# Expanssion_Bay.net
KiCad netlist of a schematic drawn in EAGLE
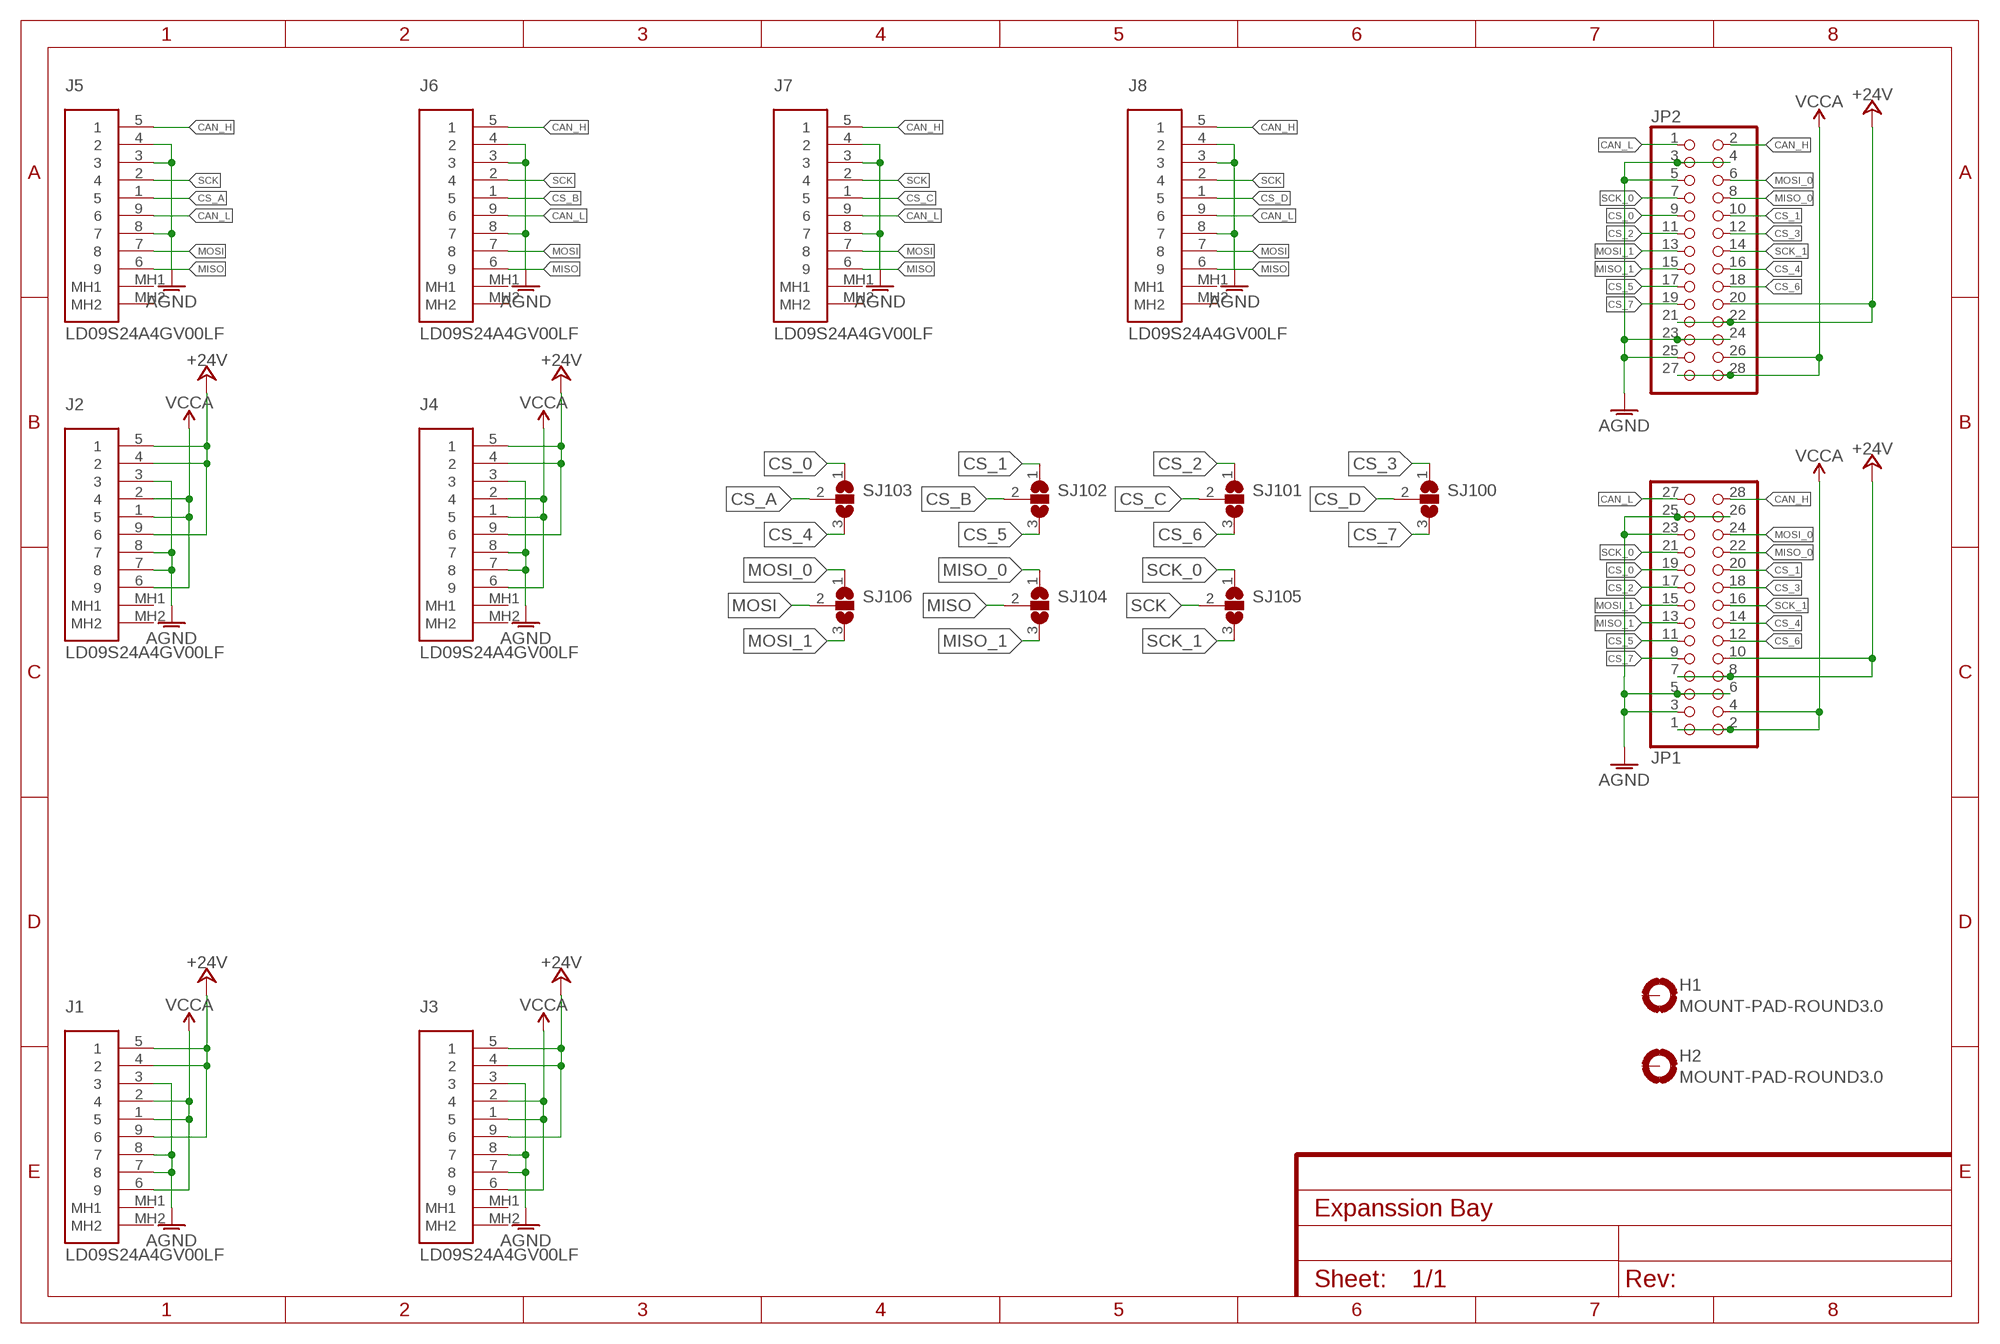
[diagram p0: schematic, sheet 1]

(export (version "E")
  (design (tool "Eeschema 10.0.6"))
  (components
    (comp (ref "H1")
      (value "MOUNT-PAD-ROUND3.0")
      (footprint "eagle-import:3,0-PAD")
      (libsource (lib "eagle-import") (part "MOUNT-PAD-ROUND3.0"))
    )
    (comp (ref "H2")
      (value "MOUNT-PAD-ROUND3.0")
      (footprint "eagle-import:3,0-PAD")
      (libsource (lib "eagle-import") (part "MOUNT-PAD-ROUND3.0"))
    )
    (comp (ref "J1")
      (value "LD09S24A4GV00LF")
      (footprint "eagle-import:LD09S24A4GV00LF")
      (fields
        (field (name "DIGIKEY_PART_NUMBER") "609-5190-ND")
        (field (name "MANUFACTURER") "Amphenol ICC (FCI)")
        (field (name "CREATED_BY") "PCBLayout.com")
      )
      (libsource (lib "eagle-import") (part "LD09S24A4GV00LF"))
    )
    (comp (ref "J2")
      (value "LD09S24A4GV00LF")
      (footprint "eagle-import:LD09S24A4GV00LF")
      (fields
        (field (name "DIGIKEY_PART_NUMBER") "609-5190-ND")
        (field (name "MANUFACTURER") "Amphenol ICC (FCI)")
        (field (name "CREATED_BY") "PCBLayout.com")
      )
      (libsource (lib "eagle-import") (part "LD09S24A4GV00LF"))
    )
    (comp (ref "J3")
      (value "LD09S24A4GV00LF")
      (footprint "eagle-import:LD09S24A4GV00LF")
      (fields
        (field (name "DIGIKEY_PART_NUMBER") "609-5190-ND")
        (field (name "MANUFACTURER") "Amphenol ICC (FCI)")
        (field (name "CREATED_BY") "PCBLayout.com")
      )
      (libsource (lib "eagle-import") (part "LD09S24A4GV00LF"))
    )
    (comp (ref "J4")
      (value "LD09S24A4GV00LF")
      (footprint "eagle-import:LD09S24A4GV00LF")
      (fields
        (field (name "DIGIKEY_PART_NUMBER") "609-5190-ND")
        (field (name "MANUFACTURER") "Amphenol ICC (FCI)")
        (field (name "CREATED_BY") "PCBLayout.com")
      )
      (libsource (lib "eagle-import") (part "LD09S24A4GV00LF"))
    )
    (comp (ref "J5")
      (value "LD09S24A4GV00LF")
      (footprint "eagle-import:LD09S24A4GV00LF")
      (fields
        (field (name "DIGIKEY_PART_NUMBER") "609-5190-ND")
        (field (name "MANUFACTURER") "Amphenol ICC (FCI)")
        (field (name "CREATED_BY") "PCBLayout.com")
      )
      (libsource (lib "eagle-import") (part "LD09S24A4GV00LF"))
    )
    (comp (ref "J6")
      (value "LD09S24A4GV00LF")
      (footprint "eagle-import:LD09S24A4GV00LF")
      (fields
        (field (name "DIGIKEY_PART_NUMBER") "609-5190-ND")
        (field (name "MANUFACTURER") "Amphenol ICC (FCI)")
        (field (name "CREATED_BY") "PCBLayout.com")
      )
      (libsource (lib "eagle-import") (part "LD09S24A4GV00LF"))
    )
    (comp (ref "J7")
      (value "LD09S24A4GV00LF")
      (footprint "eagle-import:LD09S24A4GV00LF")
      (fields
        (field (name "DIGIKEY_PART_NUMBER") "609-5190-ND")
        (field (name "MANUFACTURER") "Amphenol ICC (FCI)")
        (field (name "CREATED_BY") "PCBLayout.com")
      )
      (libsource (lib "eagle-import") (part "LD09S24A4GV00LF"))
    )
    (comp (ref "J8")
      (value "LD09S24A4GV00LF")
      (footprint "eagle-import:LD09S24A4GV00LF")
      (fields
        (field (name "DIGIKEY_PART_NUMBER") "609-5190-ND")
        (field (name "MANUFACTURER") "Amphenol ICC (FCI)")
        (field (name "CREATED_BY") "PCBLayout.com")
      )
      (libsource (lib "eagle-import") (part "LD09S24A4GV00LF"))
    )
    (comp (ref "JP1")
      (value "PINHD-2X14/90")
      (footprint "eagle-import:2X14_90")
      (libsource (lib "eagle-import") (part "PINHD-2X14/90"))
    )
    (comp (ref "JP2")
      (value "PINHD-2X14/90")
      (footprint "eagle-import:2X14_90")
      (libsource (lib "eagle-import") (part "PINHD-2X14/90"))
    )
    (comp (ref "SJ100")
      (value "SJ2W")
      (footprint "eagle-import:SJ_2")
      (libsource (lib "eagle-import") (part "SJ2W"))
    )
    (comp (ref "SJ101")
      (value "SJ2W")
      (footprint "eagle-import:SJ_2")
      (libsource (lib "eagle-import") (part "SJ2W"))
    )
    (comp (ref "SJ102")
      (value "SJ2W")
      (footprint "eagle-import:SJ_2")
      (libsource (lib "eagle-import") (part "SJ2W"))
    )
    (comp (ref "SJ103")
      (value "SJ2W")
      (footprint "eagle-import:SJ_2")
      (libsource (lib "eagle-import") (part "SJ2W"))
    )
    (comp (ref "SJ104")
      (value "SJ2W")
      (footprint "eagle-import:SJ_2")
      (libsource (lib "eagle-import") (part "SJ2W"))
    )
    (comp (ref "SJ105")
      (value "SJ2W")
      (footprint "eagle-import:SJ_2")
      (libsource (lib "eagle-import") (part "SJ2W"))
    )
    (comp (ref "SJ106")
      (value "SJ2W")
      (footprint "eagle-import:SJ_2")
      (libsource (lib "eagle-import") (part "SJ2W"))
    )
  )
  (nets
    (net (code "1") (name "+24V") (class "Default")
      (node (ref "J1") (pin "4") (pinfunction "2_4") (pintype "passive"))
      (node (ref "J1") (pin "5") (pinfunction "1_5") (pintype "passive"))
      (node (ref "J1") (pin "9") (pinfunction "6_9") (pintype "passive"))
      (node (ref "J2") (pin "4") (pinfunction "2_4") (pintype "passive"))
      (node (ref "J2") (pin "5") (pinfunction "1_5") (pintype "passive"))
      (node (ref "J2") (pin "9") (pinfunction "6_9") (pintype "passive"))
      (node (ref "J3") (pin "4") (pinfunction "2_4") (pintype "passive"))
      (node (ref "J3") (pin "5") (pinfunction "1_5") (pintype "passive"))
      (node (ref "J3") (pin "9") (pinfunction "6_9") (pintype "passive"))
      (node (ref "J4") (pin "4") (pinfunction "2_4") (pintype "passive"))
      (node (ref "J4") (pin "5") (pinfunction "1_5") (pintype "passive"))
      (node (ref "J4") (pin "9") (pinfunction "6_9") (pintype "passive"))
      (node (ref "JP1") (pin "10") (pinfunction "10_10") (pintype "passive"))
      (node (ref "JP1") (pin "7") (pinfunction "7_7") (pintype "passive"))
      (node (ref "JP1") (pin "8") (pinfunction "8_8") (pintype "passive"))
      (node (ref "JP2") (pin "20") (pinfunction "20_20") (pintype "passive"))
      (node (ref "JP2") (pin "21") (pinfunction "21_21") (pintype "passive"))
      (node (ref "JP2") (pin "22") (pinfunction "22_22") (pintype "passive"))
    )
    (net (code "2") (name "AGND") (class "Default")
      (node (ref "J1") (pin "3") (pinfunction "3_3") (pintype "passive"))
      (node (ref "J1") (pin "7") (pinfunction "8_7") (pintype "passive"))
      (node (ref "J1") (pin "8") (pinfunction "7_8") (pintype "passive"))
      (node (ref "J2") (pin "3") (pinfunction "3_3") (pintype "passive"))
      (node (ref "J2") (pin "7") (pinfunction "8_7") (pintype "passive"))
      (node (ref "J2") (pin "8") (pinfunction "7_8") (pintype "passive"))
      (node (ref "J3") (pin "3") (pinfunction "3_3") (pintype "passive"))
      (node (ref "J3") (pin "7") (pinfunction "8_7") (pintype "passive"))
      (node (ref "J3") (pin "8") (pinfunction "7_8") (pintype "passive"))
      (node (ref "J4") (pin "3") (pinfunction "3_3") (pintype "passive"))
      (node (ref "J4") (pin "7") (pinfunction "8_7") (pintype "passive"))
      (node (ref "J4") (pin "8") (pinfunction "7_8") (pintype "passive"))
      (node (ref "J5") (pin "3") (pinfunction "3_3") (pintype "passive"))
      (node (ref "J5") (pin "4") (pinfunction "2_4") (pintype "passive"))
      (node (ref "J5") (pin "8") (pinfunction "7_8") (pintype "passive"))
      (node (ref "J6") (pin "3") (pinfunction "3_3") (pintype "passive"))
      (node (ref "J6") (pin "4") (pinfunction "2_4") (pintype "passive"))
      (node (ref "J6") (pin "8") (pinfunction "7_8") (pintype "passive"))
      (node (ref "J7") (pin "3") (pinfunction "3_3") (pintype "passive"))
      (node (ref "J7") (pin "4") (pinfunction "2_4") (pintype "passive"))
      (node (ref "J7") (pin "8") (pinfunction "7_8") (pintype "passive"))
      (node (ref "J8") (pin "3") (pinfunction "3_3") (pintype "passive"))
      (node (ref "J8") (pin "4") (pinfunction "2_4") (pintype "passive"))
      (node (ref "J8") (pin "8") (pinfunction "7_8") (pintype "passive"))
      (node (ref "JP1") (pin "23") (pinfunction "23_23") (pintype "passive"))
      (node (ref "JP1") (pin "25") (pinfunction "25_25") (pintype "passive"))
      (node (ref "JP1") (pin "26") (pinfunction "26_26") (pintype "passive"))
      (node (ref "JP1") (pin "3") (pinfunction "3_3") (pintype "passive"))
      (node (ref "JP1") (pin "5") (pinfunction "5_5") (pintype "passive"))
      (node (ref "JP1") (pin "6") (pinfunction "6_6") (pintype "passive"))
      (node (ref "JP2") (pin "23") (pinfunction "23_23") (pintype "passive"))
      (node (ref "JP2") (pin "24") (pinfunction "24_24") (pintype "passive"))
      (node (ref "JP2") (pin "25") (pinfunction "25_25") (pintype "passive"))
      (node (ref "JP2") (pin "3") (pinfunction "3_3") (pintype "passive"))
      (node (ref "JP2") (pin "4") (pinfunction "4_4") (pintype "passive"))
      (node (ref "JP2") (pin "5") (pinfunction "5_5") (pintype "passive"))
    )
    (net (code "3") (name "CAN_H") (class "Default")
      (node (ref "J5") (pin "5") (pinfunction "1_5") (pintype "passive"))
      (node (ref "J6") (pin "5") (pinfunction "1_5") (pintype "passive"))
      (node (ref "J7") (pin "5") (pinfunction "1_5") (pintype "passive"))
      (node (ref "J8") (pin "5") (pinfunction "1_5") (pintype "passive"))
      (node (ref "JP1") (pin "28") (pinfunction "28_28") (pintype "passive"))
      (node (ref "JP2") (pin "2") (pinfunction "2_2") (pintype "passive"))
    )
    (net (code "4") (name "CAN_L") (class "Default")
      (node (ref "J5") (pin "9") (pinfunction "6_9") (pintype "passive"))
      (node (ref "J6") (pin "9") (pinfunction "6_9") (pintype "passive"))
      (node (ref "J7") (pin "9") (pinfunction "6_9") (pintype "passive"))
      (node (ref "J8") (pin "9") (pinfunction "6_9") (pintype "passive"))
      (node (ref "JP1") (pin "27") (pinfunction "27_27") (pintype "passive"))
      (node (ref "JP2") (pin "1") (pinfunction "1_1") (pintype "passive"))
    )
    (net (code "5") (name "CS_0") (class "Default")
      (node (ref "JP1") (pin "19") (pinfunction "19_19") (pintype "passive"))
      (node (ref "JP2") (pin "9") (pinfunction "9_9") (pintype "passive"))
      (node (ref "SJ103") (pin "1") (pinfunction "1_1") (pintype "passive"))
    )
    (net (code "6") (name "CS_1") (class "Default")
      (node (ref "JP1") (pin "20") (pinfunction "20_20") (pintype "passive"))
      (node (ref "JP2") (pin "10") (pinfunction "10_10") (pintype "passive"))
      (node (ref "SJ102") (pin "1") (pinfunction "1_1") (pintype "passive"))
    )
    (net (code "7") (name "CS_2") (class "Default")
      (node (ref "JP1") (pin "17") (pinfunction "17_17") (pintype "passive"))
      (node (ref "JP2") (pin "11") (pinfunction "11_11") (pintype "passive"))
      (node (ref "SJ101") (pin "1") (pinfunction "1_1") (pintype "passive"))
    )
    (net (code "8") (name "CS_3") (class "Default")
      (node (ref "JP1") (pin "18") (pinfunction "18_18") (pintype "passive"))
      (node (ref "JP2") (pin "12") (pinfunction "12_12") (pintype "passive"))
      (node (ref "SJ100") (pin "1") (pinfunction "1_1") (pintype "passive"))
    )
    (net (code "9") (name "CS_4") (class "Default")
      (node (ref "JP1") (pin "14") (pinfunction "14_14") (pintype "passive"))
      (node (ref "JP2") (pin "16") (pinfunction "16_16") (pintype "passive"))
      (node (ref "SJ103") (pin "3") (pinfunction "3_3") (pintype "passive"))
    )
    (net (code "10") (name "CS_5") (class "Default")
      (node (ref "JP1") (pin "11") (pinfunction "11_11") (pintype "passive"))
      (node (ref "JP2") (pin "17") (pinfunction "17_17") (pintype "passive"))
      (node (ref "SJ102") (pin "3") (pinfunction "3_3") (pintype "passive"))
    )
    (net (code "11") (name "CS_6") (class "Default")
      (node (ref "JP1") (pin "12") (pinfunction "12_12") (pintype "passive"))
      (node (ref "JP2") (pin "18") (pinfunction "18_18") (pintype "passive"))
      (node (ref "SJ101") (pin "3") (pinfunction "3_3") (pintype "passive"))
    )
    (net (code "12") (name "CS_7") (class "Default")
      (node (ref "JP1") (pin "9") (pinfunction "9_9") (pintype "passive"))
      (node (ref "JP2") (pin "19") (pinfunction "19_19") (pintype "passive"))
      (node (ref "SJ100") (pin "3") (pinfunction "3_3") (pintype "passive"))
    )
    (net (code "13") (name "CS_A") (class "Default")
      (node (ref "J5") (pin "1") (pinfunction "5_1") (pintype "passive"))
      (node (ref "SJ103") (pin "2") (pinfunction "2_2") (pintype "passive"))
    )
    (net (code "14") (name "CS_B") (class "Default")
      (node (ref "J6") (pin "1") (pinfunction "5_1") (pintype "passive"))
      (node (ref "SJ102") (pin "2") (pinfunction "2_2") (pintype "passive"))
    )
    (net (code "15") (name "CS_C") (class "Default")
      (node (ref "J7") (pin "1") (pinfunction "5_1") (pintype "passive"))
      (node (ref "SJ101") (pin "2") (pinfunction "2_2") (pintype "passive"))
    )
    (net (code "16") (name "CS_D") (class "Default")
      (node (ref "J8") (pin "1") (pinfunction "5_1") (pintype "passive"))
      (node (ref "SJ100") (pin "2") (pinfunction "2_2") (pintype "passive"))
    )
    (net (code "17") (name "MISO") (class "Default")
      (node (ref "J5") (pin "6") (pinfunction "9_6") (pintype "passive"))
      (node (ref "J6") (pin "6") (pinfunction "9_6") (pintype "passive"))
      (node (ref "J7") (pin "6") (pinfunction "9_6") (pintype "passive"))
      (node (ref "J8") (pin "6") (pinfunction "9_6") (pintype "passive"))
      (node (ref "SJ104") (pin "2") (pinfunction "2_2") (pintype "passive"))
    )
    (net (code "18") (name "MISO_0") (class "Default")
      (node (ref "JP1") (pin "22") (pinfunction "22_22") (pintype "passive"))
      (node (ref "JP2") (pin "8") (pinfunction "8_8") (pintype "passive"))
      (node (ref "SJ104") (pin "1") (pinfunction "1_1") (pintype "passive"))
    )
    (net (code "19") (name "MISO_1") (class "Default")
      (node (ref "JP1") (pin "13") (pinfunction "13_13") (pintype "passive"))
      (node (ref "JP2") (pin "15") (pinfunction "15_15") (pintype "passive"))
      (node (ref "SJ104") (pin "3") (pinfunction "3_3") (pintype "passive"))
    )
    (net (code "20") (name "MOSI") (class "Default")
      (node (ref "J5") (pin "7") (pinfunction "8_7") (pintype "passive"))
      (node (ref "J6") (pin "7") (pinfunction "8_7") (pintype "passive"))
      (node (ref "J7") (pin "7") (pinfunction "8_7") (pintype "passive"))
      (node (ref "J8") (pin "7") (pinfunction "8_7") (pintype "passive"))
      (node (ref "SJ106") (pin "2") (pinfunction "2_2") (pintype "passive"))
    )
    (net (code "21") (name "MOSI_0") (class "Default")
      (node (ref "JP1") (pin "24") (pinfunction "24_24") (pintype "passive"))
      (node (ref "JP2") (pin "6") (pinfunction "6_6") (pintype "passive"))
      (node (ref "SJ106") (pin "1") (pinfunction "1_1") (pintype "passive"))
    )
    (net (code "22") (name "MOSI_1") (class "Default")
      (node (ref "JP1") (pin "15") (pinfunction "15_15") (pintype "passive"))
      (node (ref "JP2") (pin "13") (pinfunction "13_13") (pintype "passive"))
      (node (ref "SJ106") (pin "3") (pinfunction "3_3") (pintype "passive"))
    )
    (net (code "23") (name "SCK") (class "Default")
      (node (ref "J5") (pin "2") (pinfunction "4_2") (pintype "passive"))
      (node (ref "J6") (pin "2") (pinfunction "4_2") (pintype "passive"))
      (node (ref "J7") (pin "2") (pinfunction "4_2") (pintype "passive"))
      (node (ref "J8") (pin "2") (pinfunction "4_2") (pintype "passive"))
      (node (ref "SJ105") (pin "2") (pinfunction "2_2") (pintype "passive"))
    )
    (net (code "24") (name "SCK_0") (class "Default")
      (node (ref "JP1") (pin "21") (pinfunction "21_21") (pintype "passive"))
      (node (ref "JP2") (pin "7") (pinfunction "7_7") (pintype "passive"))
      (node (ref "SJ105") (pin "1") (pinfunction "1_1") (pintype "passive"))
    )
    (net (code "25") (name "SCK_1") (class "Default")
      (node (ref "JP1") (pin "16") (pinfunction "16_16") (pintype "passive"))
      (node (ref "JP2") (pin "14") (pinfunction "14_14") (pintype "passive"))
      (node (ref "SJ105") (pin "3") (pinfunction "3_3") (pintype "passive"))
    )
    (net (code "26") (name "VCCA") (class "Default")
      (node (ref "J1") (pin "1") (pinfunction "5_1") (pintype "passive"))
      (node (ref "J1") (pin "2") (pinfunction "4_2") (pintype "passive"))
      (node (ref "J1") (pin "6") (pinfunction "9_6") (pintype "passive"))
      (node (ref "J2") (pin "1") (pinfunction "5_1") (pintype "passive"))
      (node (ref "J2") (pin "2") (pinfunction "4_2") (pintype "passive"))
      (node (ref "J2") (pin "6") (pinfunction "9_6") (pintype "passive"))
      (node (ref "J3") (pin "1") (pinfunction "5_1") (pintype "passive"))
      (node (ref "J3") (pin "2") (pinfunction "4_2") (pintype "passive"))
      (node (ref "J3") (pin "6") (pinfunction "9_6") (pintype "passive"))
      (node (ref "J4") (pin "1") (pinfunction "5_1") (pintype "passive"))
      (node (ref "J4") (pin "2") (pinfunction "4_2") (pintype "passive"))
      (node (ref "J4") (pin "6") (pinfunction "9_6") (pintype "passive"))
      (node (ref "JP1") (pin "1") (pinfunction "1_1") (pintype "passive"))
      (node (ref "JP1") (pin "2") (pinfunction "2_2") (pintype "passive"))
      (node (ref "JP1") (pin "4") (pinfunction "4_4") (pintype "passive"))
      (node (ref "JP2") (pin "26") (pinfunction "26_26") (pintype "passive"))
      (node (ref "JP2") (pin "27") (pinfunction "27_27") (pintype "passive"))
      (node (ref "JP2") (pin "28") (pinfunction "28_28") (pintype "passive"))
    )
    (net (code "27") (name "unconnected-(H1-MOUNT-PadB3,0)") (class "Default")
      (node (ref "H1") (pin "B3,0") (pinfunction "MOUNT_B3,0") (pintype "passive"))
    )
    (net (code "28") (name "unconnected-(H2-MOUNT-PadB3,0)") (class "Default")
      (node (ref "H2") (pin "B3,0") (pinfunction "MOUNT_B3,0") (pintype "passive"))
    )
    (net (code "29") (name "unconnected-(J1-PadMH1)") (class "Default")
      (node (ref "J1") (pin "MH1") (pinfunction "MH1_MH1") (pintype "passive"))
    )
    (net (code "30") (name "unconnected-(J1-PadMH2)") (class "Default")
      (node (ref "J1") (pin "MH2") (pinfunction "MH2_MH2") (pintype "passive"))
    )
    (net (code "31") (name "unconnected-(J2-PadMH1)") (class "Default")
      (node (ref "J2") (pin "MH1") (pinfunction "MH1_MH1") (pintype "passive"))
    )
    (net (code "32") (name "unconnected-(J2-PadMH2)") (class "Default")
      (node (ref "J2") (pin "MH2") (pinfunction "MH2_MH2") (pintype "passive"))
    )
    (net (code "33") (name "unconnected-(J3-PadMH1)") (class "Default")
      (node (ref "J3") (pin "MH1") (pinfunction "MH1_MH1") (pintype "passive"))
    )
    (net (code "34") (name "unconnected-(J3-PadMH2)") (class "Default")
      (node (ref "J3") (pin "MH2") (pinfunction "MH2_MH2") (pintype "passive"))
    )
    (net (code "35") (name "unconnected-(J4-PadMH1)") (class "Default")
      (node (ref "J4") (pin "MH1") (pinfunction "MH1_MH1") (pintype "passive"))
    )
    (net (code "36") (name "unconnected-(J4-PadMH2)") (class "Default")
      (node (ref "J4") (pin "MH2") (pinfunction "MH2_MH2") (pintype "passive"))
    )
    (net (code "37") (name "unconnected-(J5-PadMH1)") (class "Default")
      (node (ref "J5") (pin "MH1") (pinfunction "MH1_MH1") (pintype "passive"))
    )
    (net (code "38") (name "unconnected-(J5-PadMH2)") (class "Default")
      (node (ref "J5") (pin "MH2") (pinfunction "MH2_MH2") (pintype "passive"))
    )
    (net (code "39") (name "unconnected-(J6-PadMH1)") (class "Default")
      (node (ref "J6") (pin "MH1") (pinfunction "MH1_MH1") (pintype "passive"))
    )
    (net (code "40") (name "unconnected-(J6-PadMH2)") (class "Default")
      (node (ref "J6") (pin "MH2") (pinfunction "MH2_MH2") (pintype "passive"))
    )
    (net (code "41") (name "unconnected-(J7-PadMH1)") (class "Default")
      (node (ref "J7") (pin "MH1") (pinfunction "MH1_MH1") (pintype "passive"))
    )
    (net (code "42") (name "unconnected-(J7-PadMH2)") (class "Default")
      (node (ref "J7") (pin "MH2") (pinfunction "MH2_MH2") (pintype "passive"))
    )
    (net (code "43") (name "unconnected-(J8-PadMH1)") (class "Default")
      (node (ref "J8") (pin "MH1") (pinfunction "MH1_MH1") (pintype "passive"))
    )
    (net (code "44") (name "unconnected-(J8-PadMH2)") (class "Default")
      (node (ref "J8") (pin "MH2") (pinfunction "MH2_MH2") (pintype "passive"))
    )
  )
)
